# microd-header-adapter-board-rev2.net
KiCad netlist of a schematic drawn in Altium Designer
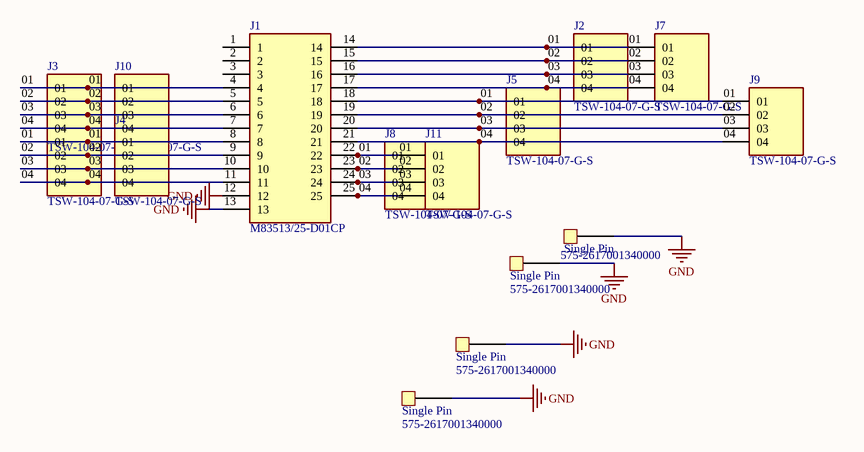
[diagram p0: microd-header-adapter-board-rev2.SchDoc]

(export (version "E")
  (design (tool "Eeschema 10.0.6"))
  (components
    (comp (ref "J1")
      (value "M83513/25-D01CP")
      (footprint "BEL_M83513/25-D01CP")
      (libsource (lib "SchlibLafe") (part "M83513/25-D01CP"))
    )
    (comp (ref "J2")
      (value "TSW-104-07-G-S")
      (footprint "SAMTEC_TSW-104-07-G-S")
      (fields (field (name "MP") "altium_native_batch"))
      (libsource (lib "SchlibLafe") (part "TSW-104-07-G-S"))
    )
    (comp (ref "J3")
      (value "TSW-104-07-G-S")
      (footprint "SAMTEC_TSW-104-07-G-S")
      (fields (field (name "MP") "altium_native_batch"))
      (libsource (lib "SchlibLafe") (part "TSW-104-07-G-S"))
    )
    (comp (ref "J4")
      (value "TSW-104-07-G-S")
      (footprint "SAMTEC_TSW-104-07-G-S")
      (fields (field (name "MP") "altium_native_batch"))
      (libsource (lib "SchlibLafe") (part "TSW-104-07-G-S"))
    )
    (comp (ref "J5")
      (value "TSW-104-07-G-S")
      (footprint "SAMTEC_TSW-104-07-G-S")
      (fields (field (name "MP") "altium_native_batch"))
      (libsource (lib "SchlibLafe") (part "TSW-104-07-G-S"))
    )
    (comp (ref "J6")
      (value "TSW-104-07-G-S")
      (footprint "SAMTEC_TSW-104-07-G-S")
      (fields (field (name "MP") "altium_native_batch"))
      (libsource (lib "SchlibLafe") (part "TSW-104-07-G-S"))
    )
    (comp (ref "J7")
      (value "TSW-104-07-G-S")
      (footprint "SAMTEC_TSW-104-07-G-S")
      (fields (field (name "MP") "altium_native_batch"))
      (libsource (lib "SchlibLafe") (part "TSW-104-07-G-S"))
    )
    (comp (ref "J8")
      (value "TSW-104-07-G-S")
      (footprint "SAMTEC_TSW-104-07-G-S")
      (fields (field (name "MP") "altium_native_batch"))
      (libsource (lib "SchlibLafe") (part "TSW-104-07-G-S"))
    )
    (comp (ref "J9")
      (value "TSW-104-07-G-S")
      (footprint "SAMTEC_TSW-104-07-G-S")
      (fields (field (name "MP") "altium_native_batch"))
      (libsource (lib "SchlibLafe") (part "TSW-104-07-G-S"))
    )
    (comp (ref "J10")
      (value "TSW-104-07-G-S")
      (footprint "SAMTEC_TSW-104-07-G-S")
      (fields (field (name "MP") "altium_native_batch"))
      (libsource (lib "SchlibLafe") (part "TSW-104-07-G-S"))
    )
    (comp (ref "J11")
      (value "TSW-104-07-G-S")
      (footprint "SAMTEC_TSW-104-07-G-S")
      (fields (field (name "MP") "altium_native_batch"))
      (libsource (lib "SchlibLafe") (part "TSW-104-07-G-S"))
    )
    (comp (ref "J12")
      (value "Single Pin")
      (footprint "Single PC Pin")
      (fields (field (name "SUPPLIER PART NUMBER 1") "575-2617001340000"))
      (libsource (lib "SchlibLafe") (part "Single PC Pin"))
    )
    (comp (ref "J13")
      (value "Single Pin")
      (footprint "Single PC Pin")
      (fields (field (name "SUPPLIER PART NUMBER 1") "575-2617001340000"))
      (libsource (lib "SchlibLafe") (part "Single PC Pin"))
    )
    (comp (ref "J14")
      (value "Single Pin")
      (footprint "Single PC Pin")
      (fields (field (name "SUPPLIER PART NUMBER 1") "575-2617001340000"))
      (libsource (lib "SchlibLafe") (part "Single PC Pin"))
    )
    (comp (ref "J15")
      (value "Single Pin")
      (footprint "Single PC Pin")
      (fields (field (name "SUPPLIER PART NUMBER 1") "575-2617001340000"))
      (libsource (lib "SchlibLafe") (part "Single PC Pin"))
    )
  )
  (nets
    (net (code "1") (name "GND") (class "Default")
      (node (ref "J1") (pin "12") (pinfunction "12_12") (pintype "passive"))
      (node (ref "J1") (pin "13") (pinfunction "13_13") (pintype "passive"))
      (node (ref "J12") (pin "1") (pinfunction "1_1") (pintype "passive"))
      (node (ref "J13") (pin "1") (pinfunction "1_1") (pintype "passive"))
      (node (ref "J14") (pin "1") (pinfunction "1_1") (pintype "passive"))
      (node (ref "J15") (pin "1") (pinfunction "1_1") (pintype "passive"))
    )
    (net (code "2") (name "Net-(J1-Pad4)") (class "Default")
      (node (ref "J1") (pin "4") (pinfunction "4_4") (pintype "passive"))
      (node (ref "J10") (pin "01") (pinfunction "01_01") (pintype "passive"))
      (node (ref "J3") (pin "01") (pinfunction "01_01") (pintype "passive"))
    )
    (net (code "3") (name "Net-(J1-Pad5)") (class "Default")
      (node (ref "J1") (pin "5") (pinfunction "5_5") (pintype "passive"))
      (node (ref "J10") (pin "02") (pinfunction "02_02") (pintype "passive"))
      (node (ref "J3") (pin "02") (pinfunction "02_02") (pintype "passive"))
    )
    (net (code "4") (name "Net-(J1-Pad6)") (class "Default")
      (node (ref "J1") (pin "6") (pinfunction "6_6") (pintype "passive"))
      (node (ref "J10") (pin "03") (pinfunction "03_03") (pintype "passive"))
      (node (ref "J3") (pin "03") (pinfunction "03_03") (pintype "passive"))
    )
    (net (code "5") (name "Net-(J1-Pad7)") (class "Default")
      (node (ref "J1") (pin "7") (pinfunction "7_7") (pintype "passive"))
      (node (ref "J10") (pin "04") (pinfunction "04_04") (pintype "passive"))
      (node (ref "J3") (pin "04") (pinfunction "04_04") (pintype "passive"))
    )
    (net (code "6") (name "Net-(J1-Pad8)") (class "Default")
      (node (ref "J1") (pin "8") (pinfunction "8_8") (pintype "passive"))
      (node (ref "J4") (pin "01") (pinfunction "01_01") (pintype "passive"))
      (node (ref "J6") (pin "01") (pinfunction "01_01") (pintype "passive"))
    )
    (net (code "7") (name "Net-(J1-Pad9)") (class "Default")
      (node (ref "J1") (pin "9") (pinfunction "9_9") (pintype "passive"))
      (node (ref "J4") (pin "02") (pinfunction "02_02") (pintype "passive"))
      (node (ref "J6") (pin "02") (pinfunction "02_02") (pintype "passive"))
    )
    (net (code "8") (name "Net-(J1-Pad10)") (class "Default")
      (node (ref "J1") (pin "10") (pinfunction "10_10") (pintype "passive"))
      (node (ref "J4") (pin "03") (pinfunction "03_03") (pintype "passive"))
      (node (ref "J6") (pin "03") (pinfunction "03_03") (pintype "passive"))
    )
    (net (code "9") (name "Net-(J1-Pad11)") (class "Default")
      (node (ref "J1") (pin "11") (pinfunction "11_11") (pintype "passive"))
      (node (ref "J4") (pin "04") (pinfunction "04_04") (pintype "passive"))
      (node (ref "J6") (pin "04") (pinfunction "04_04") (pintype "passive"))
    )
    (net (code "10") (name "Net-(J1-Pad14)") (class "Default")
      (node (ref "J1") (pin "14") (pinfunction "14_14") (pintype "passive"))
      (node (ref "J2") (pin "01") (pinfunction "01_01") (pintype "passive"))
      (node (ref "J7") (pin "01") (pinfunction "01_01") (pintype "passive"))
    )
    (net (code "11") (name "Net-(J1-Pad15)") (class "Default")
      (node (ref "J1") (pin "15") (pinfunction "15_15") (pintype "passive"))
      (node (ref "J2") (pin "02") (pinfunction "02_02") (pintype "passive"))
      (node (ref "J7") (pin "02") (pinfunction "02_02") (pintype "passive"))
    )
    (net (code "12") (name "Net-(J1-Pad16)") (class "Default")
      (node (ref "J1") (pin "16") (pinfunction "16_16") (pintype "passive"))
      (node (ref "J2") (pin "03") (pinfunction "03_03") (pintype "passive"))
      (node (ref "J7") (pin "03") (pinfunction "03_03") (pintype "passive"))
    )
    (net (code "13") (name "Net-(J1-Pad17)") (class "Default")
      (node (ref "J1") (pin "17") (pinfunction "17_17") (pintype "passive"))
      (node (ref "J2") (pin "04") (pinfunction "04_04") (pintype "passive"))
      (node (ref "J7") (pin "04") (pinfunction "04_04") (pintype "passive"))
    )
    (net (code "14") (name "Net-(J1-Pad18)") (class "Default")
      (node (ref "J1") (pin "18") (pinfunction "18_18") (pintype "passive"))
      (node (ref "J5") (pin "01") (pinfunction "01_01") (pintype "passive"))
      (node (ref "J9") (pin "01") (pinfunction "01_01") (pintype "passive"))
    )
    (net (code "15") (name "Net-(J1-Pad19)") (class "Default")
      (node (ref "J1") (pin "19") (pinfunction "19_19") (pintype "passive"))
      (node (ref "J5") (pin "02") (pinfunction "02_02") (pintype "passive"))
      (node (ref "J9") (pin "02") (pinfunction "02_02") (pintype "passive"))
    )
    (net (code "16") (name "Net-(J1-Pad20)") (class "Default")
      (node (ref "J1") (pin "20") (pinfunction "20_20") (pintype "passive"))
      (node (ref "J5") (pin "03") (pinfunction "03_03") (pintype "passive"))
      (node (ref "J9") (pin "03") (pinfunction "03_03") (pintype "passive"))
    )
    (net (code "17") (name "Net-(J1-Pad21)") (class "Default")
      (node (ref "J1") (pin "21") (pinfunction "21_21") (pintype "passive"))
      (node (ref "J5") (pin "04") (pinfunction "04_04") (pintype "passive"))
      (node (ref "J9") (pin "04") (pinfunction "04_04") (pintype "passive"))
    )
    (net (code "18") (name "Net-(J1-Pad22)") (class "Default")
      (node (ref "J1") (pin "22") (pinfunction "22_22") (pintype "passive"))
      (node (ref "J11") (pin "01") (pinfunction "01_01") (pintype "passive"))
      (node (ref "J8") (pin "01") (pinfunction "01_01") (pintype "passive"))
    )
    (net (code "19") (name "Net-(J1-Pad23)") (class "Default")
      (node (ref "J1") (pin "23") (pinfunction "23_23") (pintype "passive"))
      (node (ref "J11") (pin "02") (pinfunction "02_02") (pintype "passive"))
      (node (ref "J8") (pin "02") (pinfunction "02_02") (pintype "passive"))
    )
    (net (code "20") (name "Net-(J1-Pad24)") (class "Default")
      (node (ref "J1") (pin "24") (pinfunction "24_24") (pintype "passive"))
      (node (ref "J11") (pin "03") (pinfunction "03_03") (pintype "passive"))
      (node (ref "J8") (pin "03") (pinfunction "03_03") (pintype "passive"))
    )
    (net (code "21") (name "Net-(J1-Pad25)") (class "Default")
      (node (ref "J1") (pin "25") (pinfunction "25_25") (pintype "passive"))
      (node (ref "J11") (pin "04") (pinfunction "04_04") (pintype "passive"))
      (node (ref "J8") (pin "04") (pinfunction "04_04") (pintype "passive"))
    )
    (net (code "22") (name "unconnected-(J1-Pad1)") (class "Default")
      (node (ref "J1") (pin "1") (pinfunction "1_1") (pintype "passive"))
    )
    (net (code "23") (name "unconnected-(J1-Pad2)") (class "Default")
      (node (ref "J1") (pin "2") (pinfunction "2_2") (pintype "passive"))
    )
    (net (code "24") (name "unconnected-(J1-Pad3)") (class "Default")
      (node (ref "J1") (pin "3") (pinfunction "3_3") (pintype "passive"))
    )
  )
)
